# LOLDV22.net
KiCad netlist of a schematic drawn in EAGLE
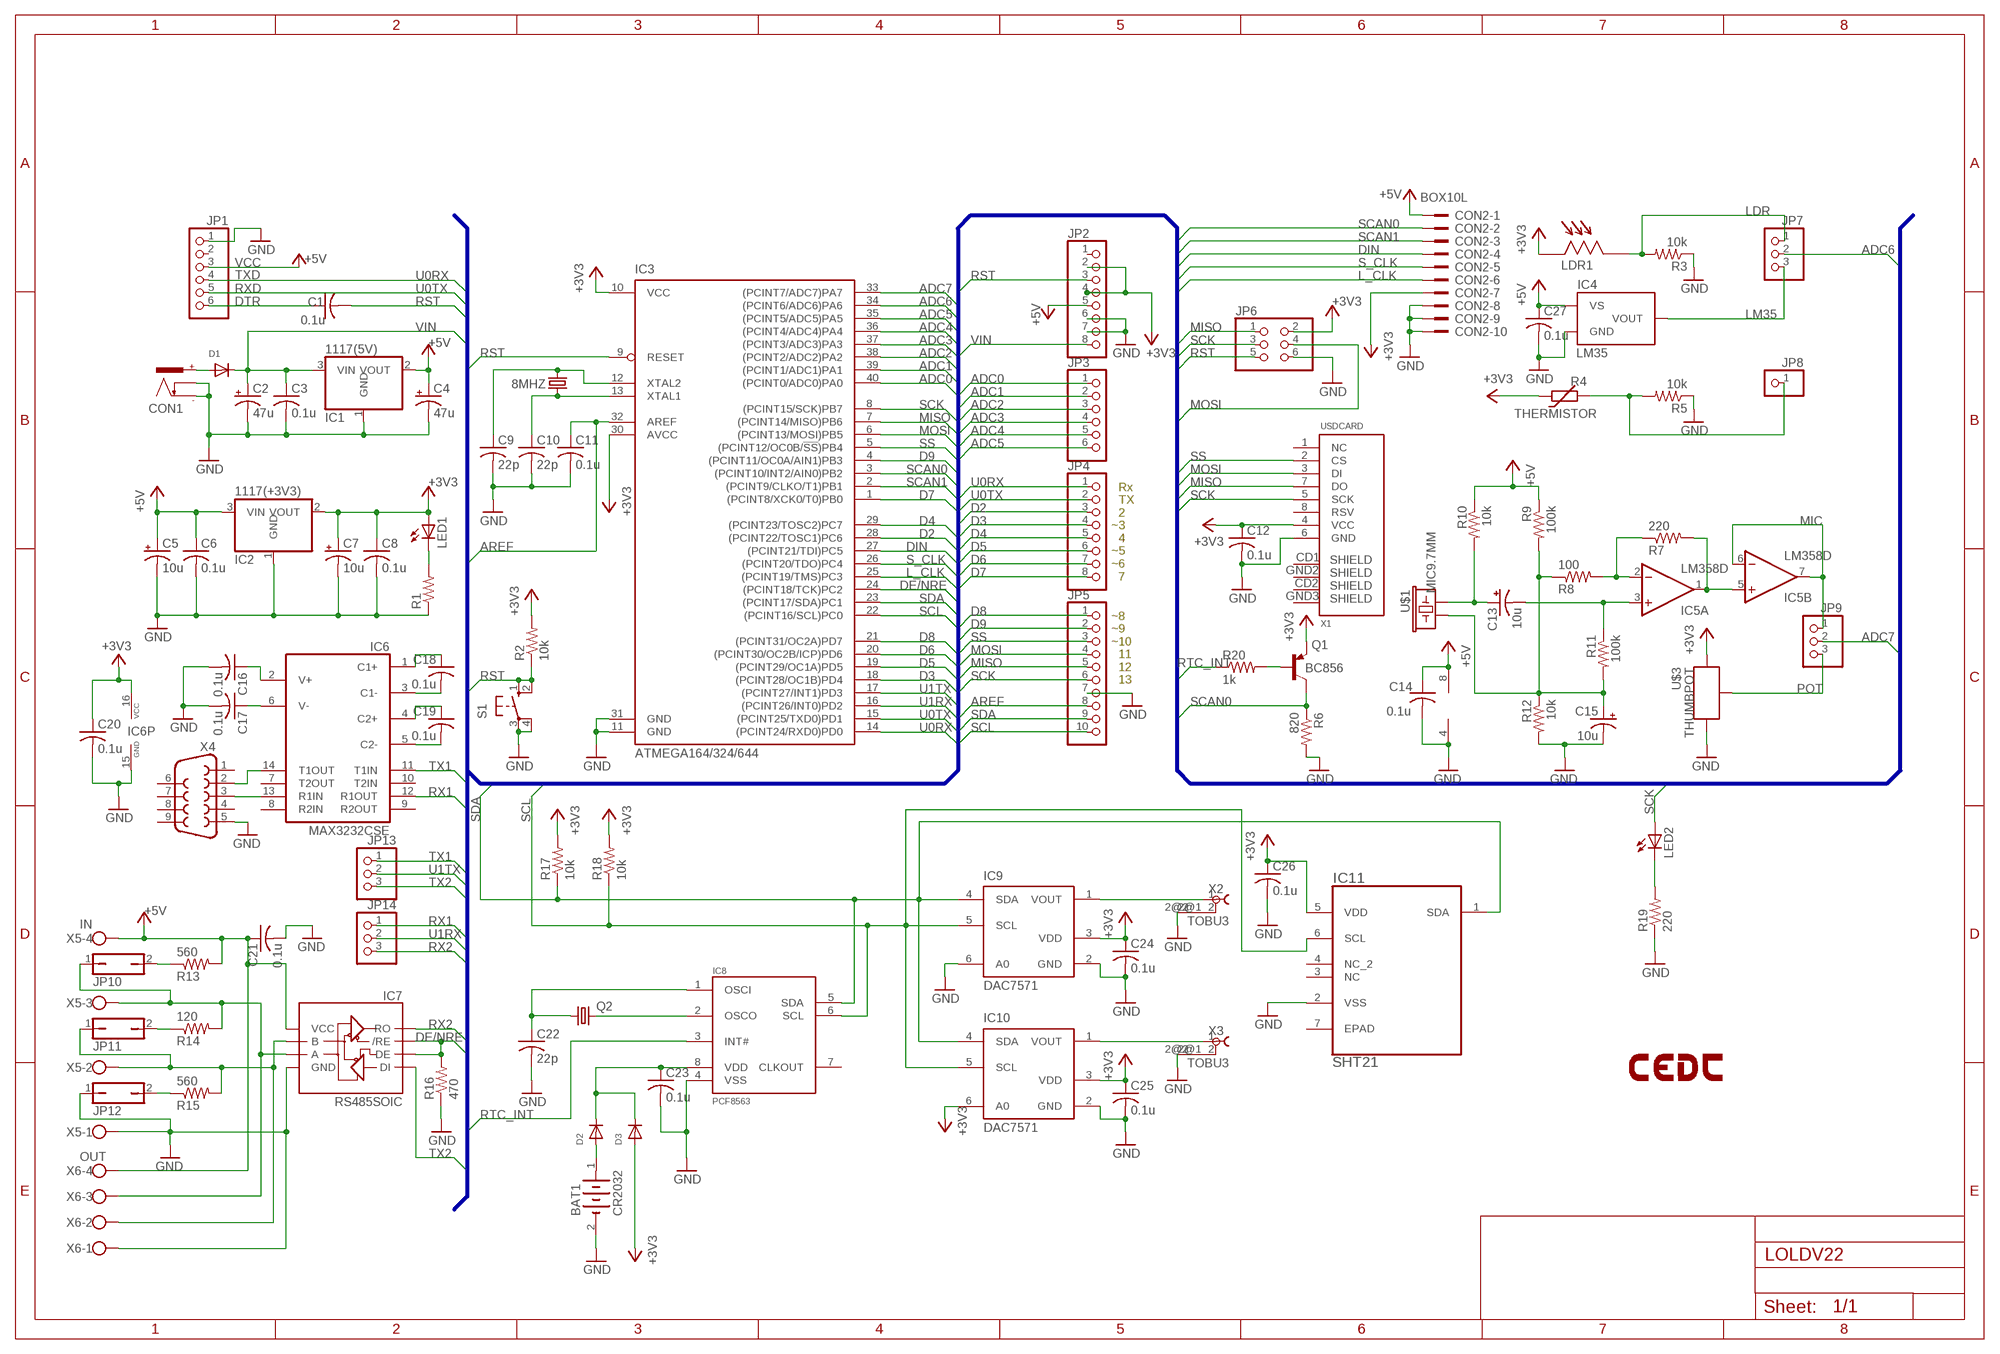
[diagram p0: schematic, sheet 1]

(export (version "E")
  (design (tool "Eeschema 10.0.6"))
  (components
    (comp (ref "8MHZ")
      (value "CRYSTALHC49US")
      (footprint "eagle-import:HC49US")
      (libsource (lib "eagle-import") (part "CRYSTALHC49US"))
    )
    (comp (ref "BAT1")
      (value "CR2032")
      (footprint "eagle-import:BATTCON_20MM")
      (libsource (lib "eagle-import") (part "CR2032"))
    )
    (comp (ref "C1")
      (value "0.1u")
      (footprint "eagle-import:C0805")
      (libsource (lib "eagle-import") (part "CEDTv73_CAP0805"))
    )
    (comp (ref "C2")
      (value "47u")
      (footprint "eagle-import:E3,5-8")
      (libsource (lib "eagle-import") (part "CPOL-USE3.5-8"))
    )
    (comp (ref "C3")
      (value "0.1u")
      (footprint "eagle-import:C0805")
      (libsource (lib "eagle-import") (part "CEDTv73_CAP0805"))
    )
    (comp (ref "C4")
      (value "47u")
      (footprint "eagle-import:E3,5-8")
      (libsource (lib "eagle-import") (part "CPOL-USE3.5-8"))
    )
    (comp (ref "C5")
      (value "10u")
      (footprint "eagle-import:C_6032-28R")
      (libsource (lib "eagle-import") (part "CAP_POL_10V"))
    )
    (comp (ref "C6")
      (value "0.1u")
      (footprint "eagle-import:C0805")
      (libsource (lib "eagle-import") (part "CEDTv73_CAP0805"))
    )
    (comp (ref "C7")
      (value "10u")
      (footprint "eagle-import:C_6032-28R")
      (libsource (lib "eagle-import") (part "CAP_POL_10V"))
    )
    (comp (ref "C8")
      (value "0.1u")
      (footprint "eagle-import:C0805")
      (libsource (lib "eagle-import") (part "CEDTv73_CAP0805"))
    )
    (comp (ref "C9")
      (value "22p")
      (footprint "eagle-import:C0805")
      (libsource (lib "eagle-import") (part "CEDTv73_CAP0805"))
    )
    (comp (ref "C10")
      (value "22p")
      (footprint "eagle-import:C0805")
      (libsource (lib "eagle-import") (part "CEDTv73_CAP0805"))
    )
    (comp (ref "C11")
      (value "0.1u")
      (footprint "eagle-import:C0805")
      (libsource (lib "eagle-import") (part "CEDTv73_CAP0805"))
    )
    (comp (ref "C12")
      (value "0.1u")
      (footprint "eagle-import:C0805")
      (libsource (lib "eagle-import") (part "CEDTv73_CAP0805"))
    )
    (comp (ref "C13")
      (value "10u")
      (footprint "eagle-import:C_6032-28R")
      (libsource (lib "eagle-import") (part "CAP_POL_10V"))
    )
    (comp (ref "C14")
      (value "0.1u")
      (footprint "eagle-import:C0805")
      (libsource (lib "eagle-import") (part "CEDTv73_CAP0805"))
    )
    (comp (ref "C15")
      (value "10u")
      (footprint "eagle-import:C_6032-28R")
      (libsource (lib "eagle-import") (part "CAP_POL_10V"))
    )
    (comp (ref "C16")
      (value "0.1u")
      (footprint "eagle-import:C0805")
      (libsource (lib "eagle-import") (part "CEDTv73_CAP0805"))
    )
    (comp (ref "C17")
      (value "0.1u")
      (footprint "eagle-import:C0805")
      (libsource (lib "eagle-import") (part "CEDTv73_CAP0805"))
    )
    (comp (ref "C18")
      (value "0.1u")
      (footprint "eagle-import:C0805")
      (libsource (lib "eagle-import") (part "CEDTv73_CAP0805"))
    )
    (comp (ref "C19")
      (value "0.1u")
      (footprint "eagle-import:C0805")
      (libsource (lib "eagle-import") (part "CEDTv73_CAP0805"))
    )
    (comp (ref "C20")
      (value "0.1u")
      (footprint "eagle-import:C0805")
      (libsource (lib "eagle-import") (part "CEDTv73_CAP0805"))
    )
    (comp (ref "C21")
      (value "0.1u")
      (footprint "eagle-import:C0805")
      (libsource (lib "eagle-import") (part "CAP0805"))
    )
    (comp (ref "C22")
      (value "22p")
      (footprint "eagle-import:C0805")
      (libsource (lib "eagle-import") (part "CEDTv73_CAP0805"))
    )
    (comp (ref "C23")
      (value "0.1u")
      (footprint "eagle-import:C0805")
      (libsource (lib "eagle-import") (part "CEDTv73_CAP0805"))
    )
    (comp (ref "C24")
      (value "0.1u")
      (footprint "eagle-import:C0805")
      (libsource (lib "eagle-import") (part "CEDTv73_CAP0805"))
    )
    (comp (ref "C25")
      (value "0.1u")
      (footprint "eagle-import:C0805")
      (libsource (lib "eagle-import") (part "CEDTv73_CAP0805"))
    )
    (comp (ref "C26")
      (value "0.1u")
      (footprint "eagle-import:C0805")
      (libsource (lib "eagle-import") (part "CEDTv73_CAP0805"))
    )
    (comp (ref "C27")
      (value "0.1u")
      (footprint "eagle-import:C0805")
      (libsource (lib "eagle-import") (part "CEDTv73_CAP0805"))
    )
    (comp (ref "CON1")
      (value "POWER_CON")
      (footprint "eagle-import:NEB21R")
      (libsource (lib "eagle-import") (part "POWER_CON"))
    )
    (comp (ref "CON2")
      (value "BOX10L")
      (footprint "eagle-import:BOX10L")
      (libsource (lib "eagle-import") (part "BOX10L"))
    )
    (comp (ref "D1")
      (value "DIODESMA")
      (footprint "eagle-import:SMADIODE")
      (libsource (lib "eagle-import") (part "DIODESMA"))
    )
    (comp (ref "D2")
      (value "DIODESMA")
      (footprint "eagle-import:SMADIODE")
      (libsource (lib "eagle-import") (part "DIODESMA"))
    )
    (comp (ref "D3")
      (value "DIODESMA")
      (footprint "eagle-import:SMADIODE")
      (libsource (lib "eagle-import") (part "DIODESMA"))
    )
    (comp (ref "IC1")
      (value "1117(5V)")
      (footprint "eagle-import:SOT223")
      (libsource (lib "eagle-import") (part "REG1117"))
    )
    (comp (ref "IC2")
      (value "1117(+3V3)")
      (footprint "eagle-import:SOT223")
      (libsource (lib "eagle-import") (part "REG1117"))
    )
    (comp (ref "IC3")
      (value "ATMEGA164/324/644")
      (footprint "eagle-import:DIP40")
      (libsource (lib "eagle-import") (part "ATMEGA164/324/644"))
    )
    (comp (ref "IC4")
      (value "LM35")
      (footprint "eagle-import:TO92")
      (libsource (lib "eagle-import") (part "LM35"))
    )
    (comp (ref "IC5")
      (value "LM358D")
      (footprint "eagle-import:SO08")
      (libsource (lib "eagle-import") (part "LM358D"))
    )
    (comp (ref "IC6")
      (value "MAX3232CSE")
      (footprint "eagle-import:SO16")
      (libsource (lib "eagle-import") (part "MAX3232SEC"))
    )
    (comp (ref "IC7")
      (value "RS485SOIC")
      (footprint "eagle-import:SO08")
      (libsource (lib "eagle-import") (part "RS485SOIC"))
    )
    (comp (ref "IC8")
      (value "PCF8563")
      (footprint "eagle-import:SOIC8")
      (libsource (lib "eagle-import") (part "PCF8563SO8"))
    )
    (comp (ref "IC9")
      (value "DAC7571")
      (footprint "eagle-import:SOT23-6")
      (libsource (lib "eagle-import") (part "DAC7571"))
    )
    (comp (ref "IC10")
      (value "DAC7571")
      (footprint "eagle-import:SOT23-6")
      (libsource (lib "eagle-import") (part "DAC7571"))
    )
    (comp (ref "IC11")
      (value "SHT21")
      (footprint "eagle-import:DFN300X300X110-7N")
      (libsource (lib "eagle-import") (part "SHT21"))
    )
    (comp (ref "JP1")
      (value "PINHD-1X6")
      (footprint "eagle-import:1X06")
      (libsource (lib "eagle-import") (part "PINHD-1X6"))
    )
    (comp (ref "JP2")
      (value "PINHD-1X8")
      (footprint "eagle-import:1X08")
      (libsource (lib "eagle-import") (part "PINHD-1X8"))
    )
    (comp (ref "JP3")
      (value "PINHD-1X6")
      (footprint "eagle-import:1X06")
      (libsource (lib "eagle-import") (part "PINHD-1X6"))
    )
    (comp (ref "JP4")
      (value "PINHD-1X8")
      (footprint "eagle-import:1X08")
      (libsource (lib "eagle-import") (part "PINHD-1X8"))
    )
    (comp (ref "JP5")
      (value "PINHD-1X10")
      (footprint "eagle-import:1X10")
      (libsource (lib "eagle-import") (part "PINHD-1X10"))
    )
    (comp (ref "JP6")
      (value "PINHD-2X3")
      (footprint "eagle-import:2X03")
      (libsource (lib "eagle-import") (part "PINHD-2X3"))
    )
    (comp (ref "JP7")
      (value "PINHD-1X3")
      (footprint "eagle-import:1X03")
      (libsource (lib "eagle-import") (part "PINHD-1X3"))
    )
    (comp (ref "JP8")
      (value "PINHD-1X1")
      (footprint "eagle-import:1X01")
      (libsource (lib "eagle-import") (part "PINHD-1X1"))
    )
    (comp (ref "JP9")
      (value "PINHD-1X3")
      (footprint "eagle-import:1X03")
      (libsource (lib "eagle-import") (part "pinhead_PINHD-1X3"))
    )
    (comp (ref "JP10")
      (value "JP1Q")
      (footprint "eagle-import:JP1")
      (libsource (lib "eagle-import") (part "JP1Q"))
    )
    (comp (ref "JP11")
      (value "JP1Q")
      (footprint "eagle-import:JP1")
      (libsource (lib "eagle-import") (part "JP1Q"))
    )
    (comp (ref "JP12")
      (value "JP1Q")
      (footprint "eagle-import:JP1")
      (libsource (lib "eagle-import") (part "JP1Q"))
    )
    (comp (ref "JP13")
      (value "PINHD-1X3")
      (footprint "eagle-import:1X03")
      (libsource (lib "eagle-import") (part "pinhead_PINHD-1X3"))
    )
    (comp (ref "JP14")
      (value "PINHD-1X3")
      (footprint "eagle-import:1X03")
      (libsource (lib "eagle-import") (part "pinhead_PINHD-1X3"))
    )
    (comp (ref "LDR1")
      (value "CDSLDR3MM")
      (footprint "eagle-import:LDR3MM")
      (libsource (lib "eagle-import") (part "CDSLDR3MM"))
    )
    (comp (ref "LED1")
      (value "LED1206")
      (footprint "eagle-import:CHIPLED_1206")
      (libsource (lib "eagle-import") (part "LED1206"))
    )
    (comp (ref "LED2")
      (value "LED1206")
      (footprint "eagle-import:CHIPLED_1206")
      (libsource (lib "eagle-import") (part "LED1206"))
    )
    (comp (ref "LOGO1")
      (value "LOGO-CEDTSILK-18MM")
      (footprint "eagle-import:LOGO-CEDT-SILK-18MM")
      (libsource (lib "eagle-import") (part "LOGO-CEDTSILK-18MM"))
    )
    (comp (ref "Q1")
      (value "BC856")
      (footprint "eagle-import:SOT23-BEC")
      (libsource (lib "eagle-import") (part "BC856SMDA"))
    )
    (comp (ref "Q2")
      (value "CRYSTALTC26H")
      (footprint "eagle-import:TC26H")
      (libsource (lib "eagle-import") (part "CRYSTALTC26H"))
    )
    (comp (ref "R1")
      (value "RESISTOR0805")
      (footprint "eagle-import:R0805")
      (libsource (lib "eagle-import") (part "CEDTv73_RESISTOR0805"))
    )
    (comp (ref "R2")
      (value "10k")
      (footprint "eagle-import:R0805")
      (libsource (lib "eagle-import") (part "CEDTv73_RESISTOR0805"))
    )
    (comp (ref "R3")
      (value "10k")
      (footprint "eagle-import:R0805")
      (libsource (lib "eagle-import") (part "CEDTv73_RESISTOR0805"))
    )
    (comp (ref "R4")
      (value "THERMISTOR")
      (footprint "eagle-import:R-5")
      (libsource (lib "eagle-import") (part "THERMISTOR-5"))
    )
    (comp (ref "R5")
      (value "10k")
      (footprint "eagle-import:R0805")
      (libsource (lib "eagle-import") (part "CEDTv73_RESISTOR0805"))
    )
    (comp (ref "R6")
      (value "820")
      (footprint "eagle-import:R0805")
      (libsource (lib "eagle-import") (part "CEDTv73_RESISTOR0805"))
    )
    (comp (ref "R7")
      (value "220")
      (footprint "eagle-import:R0805")
      (libsource (lib "eagle-import") (part "CEDTv71_RESISTOR0805"))
    )
    (comp (ref "R8")
      (value "100")
      (footprint "eagle-import:R0805")
      (libsource (lib "eagle-import") (part "CEDTv71_RESISTOR0805"))
    )
    (comp (ref "R9")
      (value "100k")
      (footprint "eagle-import:R0805")
      (libsource (lib "eagle-import") (part "CEDTv71_RESISTOR0805"))
    )
    (comp (ref "R10")
      (value "10k")
      (footprint "eagle-import:R0805")
      (libsource (lib "eagle-import") (part "CEDTv71_RESISTOR0805"))
    )
    (comp (ref "R11")
      (value "100k")
      (footprint "eagle-import:R0805")
      (libsource (lib "eagle-import") (part "CEDTv71_RESISTOR0805"))
    )
    (comp (ref "R12")
      (value "10k")
      (footprint "eagle-import:R0805")
      (libsource (lib "eagle-import") (part "CEDTv71_RESISTOR0805"))
    )
    (comp (ref "R13")
      (value "560")
      (footprint "eagle-import:R0805")
      (libsource (lib "eagle-import") (part "RESISTOR0805"))
    )
    (comp (ref "R14")
      (value "120")
      (footprint "eagle-import:R0805")
      (libsource (lib "eagle-import") (part "RESISTOR0805"))
    )
    (comp (ref "R15")
      (value "560")
      (footprint "eagle-import:R0805")
      (libsource (lib "eagle-import") (part "RESISTOR0805"))
    )
    (comp (ref "R16")
      (value "470")
      (footprint "eagle-import:R0805")
      (libsource (lib "eagle-import") (part "RESISTOR0805"))
    )
    (comp (ref "R17")
      (value "10k")
      (footprint "eagle-import:R0805")
      (libsource (lib "eagle-import") (part "CEDTv73_RESISTOR0805"))
    )
    (comp (ref "R18")
      (value "10k")
      (footprint "eagle-import:R0805")
      (libsource (lib "eagle-import") (part "CEDTv73_RESISTOR0805"))
    )
    (comp (ref "R19")
      (value "220")
      (footprint "eagle-import:R0805")
      (libsource (lib "eagle-import") (part "CEDTv73_RESISTOR0805"))
    )
    (comp (ref "R20")
      (value "1k")
      (footprint "eagle-import:R0805")
      (libsource (lib "eagle-import") (part "CEDTv73_RESISTOR0805"))
    )
    (comp (ref "S1")
      (value "10-XX")
      (footprint "eagle-import:B3F-10XX")
      (libsource (lib "eagle-import") (part "10-XX"))
    )
    (comp (ref "U$1")
      (value "MIC9.7MM")
      (footprint "eagle-import:MIC-9.7MM")
      (libsource (lib "eagle-import") (part "MIC9.7MM"))
    )
    (comp (ref "U$3")
      (value "THUMBPOT")
      (footprint "eagle-import:THUMBPOT")
      (libsource (lib "eagle-import") (part "THUMBPOT"))
    )
    (comp (ref "X1")
      (value "USDCARD")
      (footprint "eagle-import:USD-SOCKET-PUSHTYPE")
      (libsource (lib "eagle-import") (part "USDCARD"))
    )
    (comp (ref "X2")
      (value "TOBU3")
      (footprint "eagle-import:TOBU3")
      (libsource (lib "eagle-import") (part "TOBU3"))
    )
    (comp (ref "X3")
      (value "TOBU3")
      (footprint "eagle-import:TOBU3")
      (libsource (lib "eagle-import") (part "TOBU3"))
    )
    (comp (ref "X4")
      (value "DB9")
      (footprint "eagle-import:DB9")
      (libsource (lib "eagle-import") (part "DB9"))
    )
    (comp (ref "X5")
      (value "IN")
      (footprint "eagle-import:W237-4")
      (libsource (lib "eagle-import") (part "W237-4"))
    )
    (comp (ref "X6")
      (value "OUT")
      (footprint "eagle-import:W237-4")
      (libsource (lib "eagle-import") (part "W237-4"))
    )
  )
  (nets
    (net (code "1") (name "+3V3") (class "Default")
      (node (ref "C12") (pin "1") (pinfunction "1_1") (pintype "passive"))
      (node (ref "C20") (pin "1") (pinfunction "1_1") (pintype "passive"))
      (node (ref "C24") (pin "1") (pinfunction "1_1") (pintype "passive"))
      (node (ref "C25") (pin "1") (pinfunction "1_1") (pintype "passive"))
      (node (ref "C26") (pin "1") (pinfunction "1_1") (pintype "passive"))
      (node (ref "C7") (pin "+") (pinfunction "+_+") (pintype "passive"))
      (node (ref "C8") (pin "1") (pinfunction "1_1") (pintype "passive"))
      (node (ref "CON2") (pin "7") (pinfunction "KL_7") (pintype "passive"))
      (node (ref "D3") (pin "A") (pinfunction "A_A") (pintype "passive"))
      (node (ref "IC10") (pin "3") (pinfunction "VDD_3") (pintype "power_in"))
      (node (ref "IC10") (pin "6") (pinfunction "A0_6") (pintype "input"))
      (node (ref "IC11") (pin "5") (pinfunction "VDD_5") (pintype "power_in"))
      (node (ref "IC2") (pin "2") (pinfunction "VOUT_2") (pintype "output"))
      (node (ref "IC3") (pin "10") (pinfunction "VCC_10") (pintype "power_in"))
      (node (ref "IC3") (pin "30") (pinfunction "AVCC_30") (pintype "power_in"))
      (node (ref "IC6") (pin "16") (pinfunction "VCC_16") (pintype "power_in"))
      (node (ref "IC9") (pin "3") (pinfunction "VDD_3") (pintype "power_in"))
      (node (ref "JP2") (pin "2") (pinfunction "2_2") (pintype "passive"))
      (node (ref "JP2") (pin "4") (pinfunction "4_4") (pintype "passive"))
      (node (ref "JP6") (pin "2") (pinfunction "2_2") (pintype "passive"))
      (node (ref "LDR1") (pin "P$1") (pinfunction "P$1_P$1") (pintype "bidirectional"))
      (node (ref "LED1") (pin "A") (pinfunction "A_A") (pintype "passive"))
      (node (ref "Q1") (pin "E") (pinfunction "E_E") (pintype "passive"))
      (node (ref "R17") (pin "2") (pinfunction "2_2") (pintype "passive"))
      (node (ref "R18") (pin "2") (pinfunction "2_2") (pintype "passive"))
      (node (ref "R2") (pin "2") (pinfunction "2_2") (pintype "passive"))
      (node (ref "R4") (pin "1") (pinfunction "1_1") (pintype "passive"))
      (node (ref "U$3") (pin "1") (pinfunction "E_1") (pintype "passive"))
      (node (ref "X1") (pin "4") (pinfunction "VCC_4") (pintype "power_in"))
    )
    (net (code "2") (name "+5V") (class "Default")
      (node (ref "C14") (pin "1") (pinfunction "1_1") (pintype "passive"))
      (node (ref "C21") (pin "1") (pinfunction "1_1") (pintype "passive"))
      (node (ref "C27") (pin "1") (pinfunction "1_1") (pintype "passive"))
      (node (ref "C4") (pin "+") (pinfunction "+_+") (pintype "passive"))
      (node (ref "C5") (pin "+") (pinfunction "+_+") (pintype "passive"))
      (node (ref "C6") (pin "1") (pinfunction "1_1") (pintype "passive"))
      (node (ref "CON2") (pin "1") (pinfunction "KL_1") (pintype "passive"))
      (node (ref "IC1") (pin "2") (pinfunction "VOUT_2") (pintype "output"))
      (node (ref "IC2") (pin "3") (pinfunction "VIN_3") (pintype "input"))
      (node (ref "IC4") (pin "VS") (pinfunction "VS_VS") (pintype "passive"))
      (node (ref "IC5") (pin "8") (pinfunction "V+_8") (pintype "power_in"))
      (node (ref "IC7") (pin "8") (pinfunction "VCC_8") (pintype "bidirectional"))
      (node (ref "JP1") (pin "3") (pinfunction "3_3") (pintype "passive"))
      (node (ref "JP2") (pin "5") (pinfunction "5_5") (pintype "passive"))
      (node (ref "R10") (pin "1") (pinfunction "1_1") (pintype "passive"))
      (node (ref "R13") (pin "2") (pinfunction "2_2") (pintype "passive"))
      (node (ref "R9") (pin "1") (pinfunction "1_1") (pintype "passive"))
      (node (ref "X5") (pin "4") (pinfunction "KL_4") (pintype "passive"))
      (node (ref "X6") (pin "4") (pinfunction "KL_4") (pintype "passive"))
    )
    (net (code "3") (name "/ADC0") (class "Default")
      (node (ref "IC3") (pin "40") (pinfunction "(PCINT0/ADC0)PA0_40") (pintype "bidirectional"))
      (node (ref "JP3") (pin "1") (pinfunction "1_1") (pintype "passive"))
    )
    (net (code "4") (name "/ADC1") (class "Default")
      (node (ref "IC3") (pin "39") (pinfunction "(PCINT1/ADC1)PA1_39") (pintype "bidirectional"))
      (node (ref "JP3") (pin "2") (pinfunction "2_2") (pintype "passive"))
    )
    (net (code "5") (name "/ADC2") (class "Default")
      (node (ref "IC3") (pin "38") (pinfunction "(PCINT2/ADC2)PA2_38") (pintype "bidirectional"))
      (node (ref "JP3") (pin "3") (pinfunction "3_3") (pintype "passive"))
    )
    (net (code "6") (name "/ADC3") (class "Default")
      (node (ref "IC3") (pin "37") (pinfunction "(PCINT3/ADC3)PA3_37") (pintype "bidirectional"))
      (node (ref "JP3") (pin "4") (pinfunction "4_4") (pintype "passive"))
    )
    (net (code "7") (name "/ADC4") (class "Default")
      (node (ref "IC3") (pin "36") (pinfunction "(PCINT4/ADC4)PA4_36") (pintype "bidirectional"))
      (node (ref "JP3") (pin "5") (pinfunction "5_5") (pintype "passive"))
    )
    (net (code "8") (name "/ADC5") (class "Default")
      (node (ref "IC3") (pin "35") (pinfunction "(PCINT5/ADC5)PA5_35") (pintype "bidirectional"))
      (node (ref "JP3") (pin "6") (pinfunction "6_6") (pintype "passive"))
    )
    (net (code "9") (name "/ADC6") (class "Default")
      (node (ref "IC3") (pin "34") (pinfunction "(PCINT6/ADC6)PA6_34") (pintype "bidirectional"))
      (node (ref "JP7") (pin "2") (pinfunction "2_2") (pintype "passive"))
    )
    (net (code "10") (name "/ADC7") (class "Default")
      (node (ref "IC3") (pin "33") (pinfunction "(PCINT7/ADC7)PA7_33") (pintype "bidirectional"))
      (node (ref "JP9") (pin "2") (pinfunction "2_2") (pintype "passive"))
    )
    (net (code "11") (name "/AREF") (class "Default")
      (node (ref "C11") (pin "1") (pinfunction "1_1") (pintype "passive"))
      (node (ref "IC3") (pin "32") (pinfunction "AREF_32") (pintype "passive"))
      (node (ref "JP5") (pin "8") (pinfunction "8_8") (pintype "passive"))
    )
    (net (code "12") (name "/D2") (class "Default")
      (node (ref "IC3") (pin "28") (pinfunction "(PCINT22/TOSC1)PC6_28") (pintype "output"))
      (node (ref "JP4") (pin "3") (pinfunction "3_3") (pintype "passive"))
    )
    (net (code "13") (name "/D3") (class "Default")
      (node (ref "IC3") (pin "18") (pinfunction "(PCINT28/OC1B)PD4_18") (pintype "bidirectional"))
      (node (ref "JP4") (pin "4") (pinfunction "4_4") (pintype "passive"))
    )
    (net (code "14") (name "/D4") (class "Default")
      (node (ref "IC3") (pin "29") (pinfunction "(PCINT23/TOSC2)PC7_29") (pintype "output"))
      (node (ref "JP4") (pin "5") (pinfunction "5_5") (pintype "passive"))
    )
    (net (code "15") (name "/D5") (class "Default")
      (node (ref "IC3") (pin "19") (pinfunction "(PCINT29/OC1A)PD5_19") (pintype "bidirectional"))
      (node (ref "JP4") (pin "6") (pinfunction "6_6") (pintype "passive"))
    )
    (net (code "16") (name "/D6") (class "Default")
      (node (ref "IC3") (pin "20") (pinfunction "(PCINT30/OC2B/ICP)PD6_20") (pintype "bidirectional"))
      (node (ref "JP4") (pin "7") (pinfunction "7_7") (pintype "passive"))
    )
    (net (code "17") (name "/D7") (class "Default")
      (node (ref "IC3") (pin "1") (pinfunction "(PCINT8/XCK0/T0)PB0_1") (pintype "bidirectional"))
      (node (ref "JP4") (pin "8") (pinfunction "8_8") (pintype "passive"))
    )
    (net (code "18") (name "/D8") (class "Default")
      (node (ref "IC3") (pin "21") (pinfunction "(PCINT31/OC2A)PD7_21") (pintype "bidirectional"))
      (node (ref "JP5") (pin "1") (pinfunction "1_1") (pintype "passive"))
    )
    (net (code "19") (name "/D9") (class "Default")
      (node (ref "IC3") (pin "4") (pinfunction "(PCINT11/OC0A/AIN1)PB3_4") (pintype "bidirectional"))
      (node (ref "JP5") (pin "2") (pinfunction "2_2") (pintype "passive"))
    )
    (net (code "20") (name "/DE{slash}NRE") (class "Default")
      (node (ref "IC3") (pin "24") (pinfunction "(PCINT18/TCK)PC2_24") (pintype "output"))
      (node (ref "IC7") (pin "2") (pinfunction "/RE_2") (pintype "bidirectional"))
      (node (ref "IC7") (pin "3") (pinfunction "DE_3") (pintype "bidirectional"))
      (node (ref "R16") (pin "2") (pinfunction "2_2") (pintype "passive"))
    )
    (net (code "21") (name "/DIN") (class "Default")
      (node (ref "CON2") (pin "4") (pinfunction "KL_4") (pintype "passive"))
      (node (ref "IC3") (pin "27") (pinfunction "(PCINT21/TDI)PC5_27") (pintype "output"))
    )
    (net (code "22") (name "/DTR") (class "Default")
      (node (ref "C1") (pin "1") (pinfunction "1_1") (pintype "passive"))
      (node (ref "JP1") (pin "6") (pinfunction "6_6") (pintype "passive"))
    )
    (net (code "23") (name "/LDR") (class "Default")
      (node (ref "JP7") (pin "1") (pinfunction "1_1") (pintype "passive"))
      (node (ref "LDR1") (pin "P$2") (pinfunction "P$2_P$2") (pintype "bidirectional"))
      (node (ref "R3") (pin "2") (pinfunction "2_2") (pintype "passive"))
    )
    (net (code "24") (name "/LM35") (class "Default")
      (node (ref "IC4") (pin "VOUT") (pinfunction "VOUT_VOUT") (pintype "passive"))
      (node (ref "JP7") (pin "3") (pinfunction "3_3") (pintype "passive"))
    )
    (net (code "25") (name "/L_CLK") (class "Default")
      (node (ref "CON2") (pin "6") (pinfunction "KL_6") (pintype "passive"))
      (node (ref "IC3") (pin "25") (pinfunction "(PCINT19/TMS)PC3_25") (pintype "output"))
    )
    (net (code "26") (name "/MIC") (class "Default")
      (node (ref "IC5") (pin "6") (pinfunction "-IN_6") (pintype "input"))
      (node (ref "IC5") (pin "7") (pinfunction "OUT_7") (pintype "output"))
      (node (ref "JP9") (pin "1") (pinfunction "1_1") (pintype "passive"))
    )
    (net (code "27") (name "/MISO") (class "Default")
      (node (ref "IC3") (pin "7") (pinfunction "(PCINT14/MISO)PB6_7") (pintype "bidirectional"))
      (node (ref "JP5") (pin "5") (pinfunction "5_5") (pintype "passive"))
      (node (ref "JP6") (pin "1") (pinfunction "1_1") (pintype "passive"))
      (node (ref "X1") (pin "7") (pinfunction "DO_7") (pintype "output"))
    )
    (net (code "28") (name "/MOSI") (class "Default")
      (node (ref "IC3") (pin "6") (pinfunction "(PCINT13/MOSI)PB5_6") (pintype "bidirectional"))
      (node (ref "JP5") (pin "4") (pinfunction "4_4") (pintype "passive"))
      (node (ref "JP6") (pin "4") (pinfunction "4_4") (pintype "passive"))
      (node (ref "X1") (pin "3") (pinfunction "DI_3") (pintype "input"))
    )
    (net (code "29") (name "/POT") (class "Default")
      (node (ref "JP9") (pin "3") (pinfunction "3_3") (pintype "passive"))
      (node (ref "U$3") (pin "2") (pinfunction "S_2") (pintype "passive"))
    )
    (net (code "30") (name "/RST") (class "Default")
      (node (ref "C1") (pin "2") (pinfunction "2_2") (pintype "passive"))
      (node (ref "IC3") (pin "9") (pinfunction "RESET_9") (pintype "input"))
      (node (ref "JP2") (pin "3") (pinfunction "3_3") (pintype "passive"))
      (node (ref "JP6") (pin "5") (pinfunction "5_5") (pintype "passive"))
      (node (ref "R2") (pin "1") (pinfunction "1_1") (pintype "passive"))
      (node (ref "S1") (pin "1") (pinfunction "S_1") (pintype "passive"))
      (node (ref "S1") (pin "2") (pinfunction "S1_2") (pintype "passive"))
    )
    (net (code "31") (name "/RTC_INT") (class "Default")
      (node (ref "IC8") (pin "3") (pinfunction "INT#_3") (pintype "bidirectional"))
      (node (ref "R20") (pin "1") (pinfunction "1_1") (pintype "passive"))
    )
    (net (code "32") (name "/RX1") (class "Default")
      (node (ref "IC6") (pin "12") (pinfunction "R1OUT_12") (pintype "output"))
      (node (ref "JP14") (pin "1") (pinfunction "1_1") (pintype "passive"))
    )
    (net (code "33") (name "/RX2") (class "Default")
      (node (ref "IC7") (pin "1") (pinfunction "RO_1") (pintype "bidirectional"))
      (node (ref "JP14") (pin "3") (pinfunction "3_3") (pintype "passive"))
    )
    (net (code "34") (name "/SCAN0") (class "Default")
      (node (ref "CON2") (pin "2") (pinfunction "KL_2") (pintype "passive"))
      (node (ref "IC3") (pin "3") (pinfunction "(PCINT10/INT2/AIN0)PB2_3") (pintype "bidirectional"))
      (node (ref "Q1") (pin "C") (pinfunction "C_C") (pintype "passive"))
      (node (ref "R6") (pin "1") (pinfunction "1_1") (pintype "passive"))
    )
    (net (code "35") (name "/SCAN1") (class "Default")
      (node (ref "CON2") (pin "3") (pinfunction "KL_3") (pintype "passive"))
      (node (ref "IC3") (pin "2") (pinfunction "(PCINT9/CLKO/T1)PB1_2") (pintype "bidirectional"))
    )
    (net (code "36") (name "/SCK") (class "Default")
      (node (ref "IC3") (pin "8") (pinfunction "(PCINT15/SCK)PB7_8") (pintype "bidirectional"))
      (node (ref "JP5") (pin "6") (pinfunction "6_6") (pintype "passive"))
      (node (ref "JP6") (pin "3") (pinfunction "3_3") (pintype "passive"))
      (node (ref "LED2") (pin "A") (pinfunction "A_A") (pintype "passive"))
      (node (ref "X1") (pin "5") (pinfunction "SCK_5") (pintype "input"))
    )
    (net (code "37") (name "/SCL") (class "Default")
      (node (ref "IC10") (pin "5") (pinfunction "SCL_5") (pintype "bidirectional"))
      (node (ref "IC11") (pin "6") (pinfunction "SCL_6") (pintype "input"))
      (node (ref "IC3") (pin "22") (pinfunction "(PCINT16/SCL)PC0_22") (pintype "output"))
      (node (ref "IC8") (pin "6") (pinfunction "SCL_6") (pintype "bidirectional"))
      (node (ref "IC9") (pin "5") (pinfunction "SCL_5") (pintype "bidirectional"))
      (node (ref "JP5") (pin "10") (pinfunction "10_10") (pintype "passive"))
      (node (ref "R18") (pin "1") (pinfunction "1_1") (pintype "passive"))
    )
    (net (code "38") (name "/SDA") (class "Default")
      (node (ref "IC10") (pin "4") (pinfunction "SDA_4") (pintype "bidirectional"))
      (node (ref "IC11") (pin "1") (pinfunction "SDA_1") (pintype "bidirectional"))
      (node (ref "IC3") (pin "23") (pinfunction "(PCINT17/SDA)PC1_23") (pintype "output"))
      (node (ref "IC8") (pin "5") (pinfunction "SDA_5") (pintype "bidirectional"))
      (node (ref "IC9") (pin "4") (pinfunction "SDA_4") (pintype "bidirectional"))
      (node (ref "JP5") (pin "9") (pinfunction "9_9") (pintype "passive"))
      (node (ref "R17") (pin "1") (pinfunction "1_1") (pintype "passive"))
    )
    (net (code "39") (name "/SS") (class "Default")
      (node (ref "IC3") (pin "5") (pinfunction "(PCINT12/OC0B/~{SS})PB4_5") (pintype "bidirectional"))
      (node (ref "JP5") (pin "3") (pinfunction "3_3") (pintype "passive"))
      (node (ref "X1") (pin "2") (pinfunction "CS_2") (pintype "bidirectional"))
    )
    (net (code "40") (name "/S_CLK") (class "Default")
      (node (ref "CON2") (pin "5") (pinfunction "KL_5") (pintype "passive"))
      (node (ref "IC3") (pin "26") (pinfunction "(PCINT20/TDO)PC4_26") (pintype "output"))
    )
    (net (code "41") (name "/TX1") (class "Default")
      (node (ref "IC6") (pin "11") (pinfunction "T1IN_11") (pintype "input"))
      (node (ref "JP13") (pin "1") (pinfunction "1_1") (pintype "passive"))
    )
    (net (code "42") (name "/TX2") (class "Default")
      (node (ref "IC7") (pin "4") (pinfunction "DI_4") (pintype "bidirectional"))
      (node (ref "JP13") (pin "3") (pinfunction "3_3") (pintype "passive"))
    )
    (net (code "43") (name "/U0RX") (class "Default")
      (node (ref "IC3") (pin "14") (pinfunction "(PCINT24/RXD0)PD0_14") (pintype "bidirectional"))
      (node (ref "JP1") (pin "4") (pinfunction "4_4") (pintype "passive"))
      (node (ref "JP4") (pin "1") (pinfunction "1_1") (pintype "passive"))
    )
    (net (code "44") (name "/U0TX") (class "Default")
      (node (ref "IC3") (pin "15") (pinfunction "(PCINT25/TXD0)PD1_15") (pintype "bidirectional"))
      (node (ref "JP1") (pin "5") (pinfunction "5_5") (pintype "passive"))
      (node (ref "JP4") (pin "2") (pinfunction "2_2") (pintype "passive"))
    )
    (net (code "45") (name "/U1RX") (class "Default")
      (node (ref "IC3") (pin "16") (pinfunction "(PCINT26/INT0)PD2_16") (pintype "bidirectional"))
      (node (ref "JP14") (pin "2") (pinfunction "2_2") (pintype "passive"))
    )
    (net (code "46") (name "/U1TX") (class "Default")
      (node (ref "IC3") (pin "17") (pinfunction "(PCINT27/INT1)PD3_17") (pintype "bidirectional"))
      (node (ref "JP13") (pin "2") (pinfunction "2_2") (pintype "passive"))
    )
    (net (code "47") (name "/VIN") (class "Default")
      (node (ref "C2") (pin "+") (pinfunction "+_+") (pintype "passive"))
      (node (ref "C3") (pin "1") (pinfunction "1_1") (pintype "passive"))
      (node (ref "D1") (pin "C") (pinfunction "C_C") (pintype "passive"))
      (node (ref "IC1") (pin "3") (pinfunction "VIN_3") (pintype "input"))
      (node (ref "JP2") (pin "8") (pinfunction "8_8") (pintype "passive"))
    )
    (net (code "48") (name "GND") (class "Default")
      (node (ref "BAT1") (pin "2") (pinfunction "-_2") (pintype "passive"))
      (node (ref "C10") (pin "2") (pinfunction "2_2") (pintype "passive"))
      (node (ref "C11") (pin "2") (pinfunction "2_2") (pintype "passive"))
      (node (ref "C12") (pin "2") (pinfunction "2_2") (pintype "passive"))
      (node (ref "C14") (pin "2") (pinfunction "2_2") (pintype "passive"))
      (node (ref "C15") (pin "-") (pinfunction "-_-") (pintype "passive"))
      (node (ref "C16") (pin "2") (pinfunction "2_2") (pintype "passive"))
      (node (ref "C17") (pin "2") (pinfunction "2_2") (pintype "passive"))
      (node (ref "C2") (pin "-") (pinfunction "-_-") (pintype "passive"))
      (node (ref "C20") (pin "2") (pinfunction "2_2") (pintype "passive"))
      (node (ref "C21") (pin "2") (pinfunction "2_2") (pintype "passive"))
      (node (ref "C22") (pin "2") (pinfunction "2_2") (pintype "passive"))
      (node (ref "C23") (pin "2") (pinfunction "2_2") (pintype "passive"))
      (node (ref "C24") (pin "2") (pinfunction "2_2") (pintype "passive"))
      (node (ref "C25") (pin "2") (pinfunction "2_2") (pintype "passive"))
      (node (ref "C26") (pin "2") (pinfunction "2_2") (pintype "passive"))
      (node (ref "C27") (pin "2") (pinfunction "2_2") (pintype "passive"))
      (node (ref "C3") (pin "2") (pinfunction "2_2") (pintype "passive"))
      (node (ref "C4") (pin "-") (pinfunction "-_-") (pintype "passive"))
      (node (ref "C5") (pin "-") (pinfunction "-_-") (pintype "passive"))
      (node (ref "C6") (pin "2") (pinfunction "2_2") (pintype "passive"))
      (node (ref "C7") (pin "-") (pinfunction "-_-") (pintype "passive"))
      (node (ref "C8") (pin "2") (pinfunction "2_2") (pintype "passive"))
      (node (ref "C9") (pin "2") (pinfunction "2_2") (pintype "passive"))
      (node (ref "CON1") (pin "-") (pinfunction "-_-") (pintype "passive"))
      (node (ref "CON1") (pin "C") (pinfunction "C_C") (pintype "passive"))
      (node (ref "CON2") (pin "10") (pinfunction "KL_10") (pintype "passive"))
      (node (ref "CON2") (pin "8") (pinfunction "KL_8") (pintype "passive"))
      (node (ref "CON2") (pin "9") (pinfunction "KL_9") (pintype "passive"))
      (node (ref "IC1") (pin "1") (pinfunction "GND_1") (pintype "power_in"))
      (node (ref "IC10") (pin "2") (pinfunction "GND_2") (pintype "power_in"))
      (node (ref "IC11") (pin "2") (pinfunction "VSS_2") (pintype "power_in"))
      (node (ref "IC2") (pin "1") (pinfunction "GND_1") (pintype "power_in"))
      (node (ref "IC3") (pin "11") (pinfunction "GND_11") (pintype "power_in"))
      (node (ref "IC3") (pin "31") (pinfunction "GND_31") (pintype "power_in"))
      (node (ref "IC4") (pin "GND") (pinfunction "GND_GND") (pintype "passive"))
      (node (ref "IC5") (pin "4") (pinfunction "V-_4") (pintype "power_in"))
      (node (ref "IC6") (pin "15") (pinfunction "GND_15") (pintype "power_in"))
      (node (ref "IC7") (pin "5") (pinfunction "GND_5") (pintype "bidirectional"))
      (node (ref "IC8") (pin "4") (pinfunction "VSS_4") (pintype "bidirectional"))
      (node (ref "IC9") (pin "2") (pinfunction "GND_2") (pintype "power_in"))
      (node (ref "IC9") (pin "6") (pinfunction "A0_6") (pintype "input"))
      (node (ref "JP1") (pin "1") (pinfunction "1_1") (pintype "passive"))
      (node (ref "JP12") (pin "1") (pinfunction "1_1") (pintype "passive"))
      (node (ref "JP2") (pin "6") (pinfunction "6_6") (pintype "passive"))
      (node (ref "JP2") (pin "7") (pinfunction "7_7") (pintype "passive"))
      (node (ref "JP5") (pin "7") (pinfunction "7_7") (pintype "passive"))
      (node (ref "JP6") (pin "6") (pinfunction "6_6") (pintype "passive"))
      (node (ref "R1") (pin "1") (pinfunction "1_1") (pintype "passive"))
      (node (ref "R12") (pin "2") (pinfunction "2_2") (pintype "passive"))
      (node (ref "R16") (pin "1") (pinfunction "1_1") (pintype "passive"))
      (node (ref "R19") (pin "1") (pinfunction "1_1") (pintype "passive"))
      (node (ref "R3") (pin "1") (pinfunction "1_1") (pintype "passive"))
      (node (ref "R5") (pin "1") (pinfunction "1_1") (pintype "passive"))
      (node (ref "R6") (pin "2") (pinfunction "2_2") (pintype "passive"))
      (node (ref "S1") (pin "3") (pinfunction "P_3") (pintype "passive"))
      (node (ref "S1") (pin "4") (pinfunction "P1_4") (pintype "passive"))
      (node (ref "U$3") (pin "3") (pinfunction "A_3") (pintype "passive"))
      (node (ref "X1") (pin "6") (pinfunction "GND_6") (pintype "power_in"))
      (node (ref "X2") (pin "2@2") (pinfunction "4_2@2") (pintype "passive"))
      (node (ref "X3") (pin "2@2") (pinfunction "4_2@2") (pintype "passive"))
      (node (ref "X4") (pin "5") (pinfunction "5_5") (pintype "passive"))
      (node (ref "X5") (pin "1") (pinfunction "KL_1") (pintype "passive"))
      (node (ref "X6") (pin "1") (pinfunction "KL_1") (pintype "passive"))
    )
    (net (code "49") (name "Net-(BAT1-+)") (class "Default")
      (node (ref "BAT1") (pin "1") (pinfunction "+_1") (pintype "passive"))
      (node (ref "D2") (pin "A") (pinfunction "A_A") (pintype "passive"))
    )
    (net (code "50") (name "Net-(C13-Pad+)") (class "Default")
      (node (ref "C13") (pin "+") (pinfunction "+_+") (pintype "passive"))
      (node (ref "R10") (pin "2") (pinfunction "2_2") (pintype "passive"))
      (node (ref "U$1") (pin "1") (pinfunction "1_1") (pintype "passive"))
    )
    (net (code "51") (name "Net-(C15-Pad+)") (class "Default")
      (node (ref "C15") (pin "+") (pinfunction "+_+") (pintype "passive"))
      (node (ref "R11") (pin "2") (pinfunction "2_2") (pintype "passive"))
      (node (ref "R12") (pin "1") (pinfunction "1_1") (pintype "passive"))
      (node (ref "R8") (pin "1") (pinfunction "1_1") (pintype "passive"))
      (node (ref "R9") (pin "2") (pinfunction "2_2") (pintype "passive"))
      (node (ref "U$1") (pin "2") (pinfunction "2_2") (pintype "passive"))
    )
    (net (code "52") (name "Net-(CON1-Pad+)") (class "Default")
      (node (ref "CON1") (pin "+") (pinfunction "+_+") (pintype "passive"))
      (node (ref "D1") (pin "A") (pinfunction "A_A") (pintype "passive"))
    )
    (net (code "53") (name "Net-(IC3-XTAL1)") (class "Default")
      (node (ref "8MHZ") (pin "1") (pinfunction "1_1") (pintype "passive"))
      (node (ref "C10") (pin "1") (pinfunction "1_1") (pintype "passive"))
      (node (ref "IC3") (pin "13") (pinfunction "XTAL1_13") (pintype "bidirectional"))
    )
    (net (code "54") (name "Net-(IC3-XTAL2)") (class "Default")
      (node (ref "8MHZ") (pin "2") (pinfunction "2_2") (pintype "passive"))
      (node (ref "C9") (pin "1") (pinfunction "1_1") (pintype "passive"))
      (node (ref "IC3") (pin "12") (pinfunction "XTAL2_12") (pintype "bidirectional"))
    )
    (net (code "55") (name "Net-(IC5A-+IN)") (class "Default")
      (node (ref "C13") (pin "-") (pinfunction "-_-") (pintype "passive"))
      (node (ref "IC5") (pin "3") (pinfunction "+IN_3") (pintype "input"))
      (node (ref "R11") (pin "1") (pinfunction "1_1") (pintype "passive"))
    )
    (net (code "56") (name "Net-(IC5A--IN)") (class "Default")
      (node (ref "IC5") (pin "2") (pinfunction "-IN_2") (pintype "input"))
      (node (ref "R7") (pin "1") (pinfunction "1_1") (pintype "passive"))
      (node (ref "R8") (pin "2") (pinfunction "2_2") (pintype "passive"))
    )
    (net (code "57") (name "Net-(IC5A-OUT)") (class "Default")
      (node (ref "IC5") (pin "1") (pinfunction "OUT_1") (pintype "output"))
      (node (ref "IC5") (pin "5") (pinfunction "+IN_5") (pintype "input"))
      (node (ref "R7") (pin "2") (pinfunction "2_2") (pintype "passive"))
    )
    (net (code "58") (name "Net-(IC6A-C1+)") (class "Default")
      (node (ref "C18") (pin "1") (pinfunction "1_1") (pintype "passive"))
      (node (ref "IC6") (pin "1") (pinfunction "C1+_1") (pintype "bidirectional"))
    )
    (net (code "59") (name "Net-(IC6A-C1-)") (class "Default")
      (node (ref "C18") (pin "2") (pinfunction "2_2") (pintype "passive"))
      (node (ref "IC6") (pin "3") (pinfunction "C1-_3") (pintype "bidirectional"))
    )
    (net (code "60") (name "Net-(IC6A-C2+)") (class "Default")
      (node (ref "C19") (pin "1") (pinfunction "1_1") (pintype "passive"))
      (node (ref "IC6") (pin "4") (pinfunction "C2+_4") (pintype "bidirectional"))
    )
    (net (code "61") (name "Net-(IC6A-C2-)") (class "Default")
      (node (ref "C19") (pin "2") (pinfunction "2_2") (pintype "passive"))
      (node (ref "IC6") (pin "5") (pinfunction "C2-_5") (pintype "bidirectional"))
    )
    (net (code "62") (name "Net-(IC6A-R1IN)") (class "Default")
      (node (ref "IC6") (pin "13") (pinfunction "R1IN_13") (pintype "input"))
      (node (ref "X4") (pin "3") (pinfunction "3_3") (pintype "passive"))
    )
    (net (code "63") (name "Net-(IC6A-T1OUT)") (class "Default")
      (node (ref "IC6") (pin "14") (pinfunction "T1OUT_14") (pintype "output"))
      (node (ref "X4") (pin "2") (pinfunction "2_2") (pintype "passive"))
    )
    (net (code "64") (name "Net-(IC6A-V+)") (class "Default")
      (node (ref "C16") (pin "1") (pinfunction "1_1") (pintype "passive"))
      (node (ref "IC6") (pin "2") (pinfunction "V+_2") (pintype "bidirectional"))
    )
    (net (code "65") (name "Net-(IC6A-V-)") (class "Default")
      (node (ref "C17") (pin "1") (pinfunction "1_1") (pintype "passive"))
      (node (ref "IC6") (pin "6") (pinfunction "V-_6") (pintype "bidirectional"))
    )
    (net (code "66") (name "Net-(IC7-A)") (class "Default")
      (node (ref "IC7") (pin "6") (pinfunction "A_6") (pintype "bidirectional"))
      (node (ref "JP10") (pin "1") (pinfunction "1_1") (pintype "passive"))
      (node (ref "R14") (pin "2") (pinfunction "2_2") (pintype "passive"))
      (node (ref "X5") (pin "3") (pinfunction "KL_3") (pintype "passive"))
      (node (ref "X6") (pin "3") (pinfunction "KL_3") (pintype "passive"))
    )
    (net (code "67") (name "Net-(IC7-B)") (class "Default")
      (node (ref "IC7") (pin "7") (pinfunction "B_7") (pintype "bidirectional"))
      (node (ref "JP11") (pin "1") (pinfunction "1_1") (pintype "passive"))
      (node (ref "R15") (pin "2") (pinfunction "2_2") (pintype "passive"))
      (node (ref "X5") (pin "2") (pinfunction "KL_2") (pintype "passive"))
      (node (ref "X6") (pin "2") (pinfunction "KL_2") (pintype "passive"))
    )
    (net (code "68") (name "Net-(IC8-OSCI)") (class "Default")
      (node (ref "C22") (pin "1") (pinfunction "1_1") (pintype "passive"))
      (node (ref "IC8") (pin "1") (pinfunction "OSCI_1") (pintype "bidirectional"))
      (node (ref "Q2") (pin "1") (pinfunction "1_1") (pintype "passive"))
    )
    (net (code "69") (name "Net-(IC8-OSCO)") (class "Default")
      (node (ref "IC8") (pin "2") (pinfunction "OSCO_2") (pintype "bidirectional"))
      (node (ref "Q2") (pin "2") (pinfunction "2_2") (pintype "passive"))
    )
    (net (code "70") (name "Net-(IC8-VDD)") (class "Default")
      (node (ref "C23") (pin "1") (pinfunction "1_1") (pintype "passive"))
      (node (ref "D2") (pin "C") (pinfunction "C_C") (pintype "passive"))
      (node (ref "D3") (pin "C") (pinfunction "C_C") (pintype "passive"))
      (node (ref "IC8") (pin "8") (pinfunction "VDD_8") (pintype "bidirectional"))
    )
    (net (code "71") (name "Net-(IC9-VOUT)") (class "Default")
      (node (ref "IC9") (pin "1") (pinfunction "VOUT_1") (pintype "output"))
      (node (ref "X2") (pin "1") (pinfunction "1_1") (pintype "passive"))
    )
    (net (code "72") (name "Net-(IC10-VOUT)") (class "Default")
      (node (ref "IC10") (pin "1") (pinfunction "VOUT_1") (pintype "output"))
      (node (ref "X3") (pin "1") (pinfunction "1_1") (pintype "passive"))
    )
    (net (code "73") (name "Net-(JP8-Pad1)") (class "Default")
      (node (ref "JP8") (pin "1") (pinfunction "1_1") (pintype "passive"))
      (node (ref "R4") (pin "2") (pinfunction "2_2") (pintype "passive"))
      (node (ref "R5") (pin "2") (pinfunction "2_2") (pintype "passive"))
    )
    (net (code "74") (name "Net-(JP10-Pad2)") (class "Default")
      (node (ref "JP10") (pin "2") (pinfunction "2_2") (pintype "passive"))
      (node (ref "R13") (pin "1") (pinfunction "1_1") (pintype "passive"))
    )
    (net (code "75") (name "Net-(JP11-Pad2)") (class "Default")
      (node (ref "JP11") (pin "2") (pinfunction "2_2") (pintype "passive"))
      (node (ref "R14") (pin "1") (pinfunction "1_1") (pintype "passive"))
    )
    (net (code "76") (name "Net-(JP12-Pad2)") (class "Default")
      (node (ref "JP12") (pin "2") (pinfunction "2_2") (pintype "passive"))
      (node (ref "R15") (pin "1") (pinfunction "1_1") (pintype "passive"))
    )
    (net (code "77") (name "Net-(LED1-PadC)") (class "Default")
      (node (ref "LED1") (pin "C") (pinfunction "C_C") (pintype "passive"))
      (node (ref "R1") (pin "2") (pinfunction "2_2") (pintype "passive"))
    )
    (net (code "78") (name "Net-(LED2-PadC)") (class "Default")
      (node (ref "LED2") (pin "C") (pinfunction "C_C") (pintype "passive"))
      (node (ref "R19") (pin "2") (pinfunction "2_2") (pintype "passive"))
    )
    (net (code "79") (name "Net-(Q1-PadB)") (class "Default")
      (node (ref "Q1") (pin "B") (pinfunction "B_B") (pintype "passive"))
      (node (ref "R20") (pin "2") (pinfunction "2_2") (pintype "passive"))
    )
    (net (code "80") (name "unconnected-(IC6A-R2IN-Pad8)") (class "Default")
      (node (ref "IC6") (pin "8") (pinfunction "R2IN_8") (pintype "input"))
    )
    (net (code "81") (name "unconnected-(IC6A-R2OUT-Pad9)") (class "Default")
      (node (ref "IC6") (pin "9") (pinfunction "R2OUT_9") (pintype "output"))
    )
    (net (code "82") (name "unconnected-(IC6A-T2IN-Pad10)") (class "Default")
      (node (ref "IC6") (pin "10") (pinfunction "T2IN_10") (pintype "input"))
    )
    (net (code "83") (name "unconnected-(IC6A-T2OUT-Pad7)") (class "Default")
      (node (ref "IC6") (pin "7") (pinfunction "T2OUT_7") (pintype "output"))
    )
    (net (code "84") (name "unconnected-(IC8-CLKOUT-Pad7)") (class "Default")
      (node (ref "IC8") (pin "7") (pinfunction "CLKOUT_7") (pintype "bidirectional"))
    )
    (net (code "85") (name "unconnected-(IC11-EPAD-Pad7)") (class "Default")
      (node (ref "IC11") (pin "7") (pinfunction "EPAD_7") (pintype "passive"))
    )
    (net (code "86") (name "unconnected-(IC11-NC-Pad3)") (class "Default")
      (node (ref "IC11") (pin "3") (pinfunction "NC_3") (pintype "no_connect"))
    )
    (net (code "87") (name "unconnected-(IC11-NC_2-Pad4)") (class "Default")
      (node (ref "IC11") (pin "4") (pinfunction "NC_2_4") (pintype "no_connect"))
    )
    (net (code "88") (name "unconnected-(JP1-Pad2)") (class "Default")
      (node (ref "JP1") (pin "2") (pinfunction "2_2") (pintype "passive"))
    )
    (net (code "89") (name "unconnected-(JP2-Pad1)") (class "Default")
      (node (ref "JP2") (pin "1") (pinfunction "1_1") (pintype "passive"))
    )
    (net (code "90") (name "unconnected-(X1-NC-Pad1)") (class "Default")
      (node (ref "X1") (pin "1") (pinfunction "NC_1") (pintype "passive"))
    )
    (net (code "91") (name "unconnected-(X1-PadCD1)") (class "Default")
      (node (ref "X1") (pin "CD1") (pinfunction "CD1_CD1") (pintype "passive"))
    )
    (net (code "92") (name "unconnected-(X1-PadCD2)") (class "Default")
      (node (ref "X1") (pin "CD2") (pinfunction "CD2_CD2") (pintype "passive"))
    )
    (net (code "93") (name "unconnected-(X1-PadGND2)") (class "Default")
      (node (ref "X1") (pin "GND2") (pinfunction "GND2_GND2") (pintype "passive"))
    )
    (net (code "94") (name "unconnected-(X1-PadGND3)") (class "Default")
      (node (ref "X1") (pin "GND3") (pinfunction "GND3_GND3") (pintype "passive"))
    )
    (net (code "95") (name "unconnected-(X1-RSV-Pad8)") (class "Default")
      (node (ref "X1") (pin "8") (pinfunction "RSV_8") (pintype "passive"))
    )
    (net (code "96") (name "unconnected-(X2-3-Pad2@1)") (class "Default")
      (node (ref "X2") (pin "2@1") (pinfunction "3_2@1") (pintype "passive"))
    )
    (net (code "97") (name "unconnected-(X2-Pad2)") (class "Default")
      (node (ref "X2") (pin "2") (pinfunction "2_2") (pintype "passive"))
    )
    (net (code "98") (name "unconnected-(X3-3-Pad2@1)") (class "Default")
      (node (ref "X3") (pin "2@1") (pinfunction "3_2@1") (pintype "passive"))
    )
    (net (code "99") (name "unconnected-(X3-Pad2)") (class "Default")
      (node (ref "X3") (pin "2") (pinfunction "2_2") (pintype "passive"))
    )
    (net (code "100") (name "unconnected-(X4-Pad1)") (class "Default")
      (node (ref "X4") (pin "1") (pinfunction "1_1") (pintype "passive"))
    )
    (net (code "101") (name "unconnected-(X4-Pad4)") (class "Default")
      (node (ref "X4") (pin "4") (pinfunction "4_4") (pintype "passive"))
    )
    (net (code "102") (name "unconnected-(X4-Pad6)") (class "Default")
      (node (ref "X4") (pin "6") (pinfunction "6_6") (pintype "passive"))
    )
    (net (code "103") (name "unconnected-(X4-Pad7)") (class "Default")
      (node (ref "X4") (pin "7") (pinfunction "7_7") (pintype "passive"))
    )
    (net (code "104") (name "unconnected-(X4-Pad8)") (class "Default")
      (node (ref "X4") (pin "8") (pinfunction "8_8") (pintype "passive"))
    )
    (net (code "105") (name "unconnected-(X4-Pad9)") (class "Default")
      (node (ref "X4") (pin "9") (pinfunction "9_9") (pintype "passive"))
    )
  )
)
